# Sheet2.net
KiCad netlist of a schematic drawn in Altium Designer
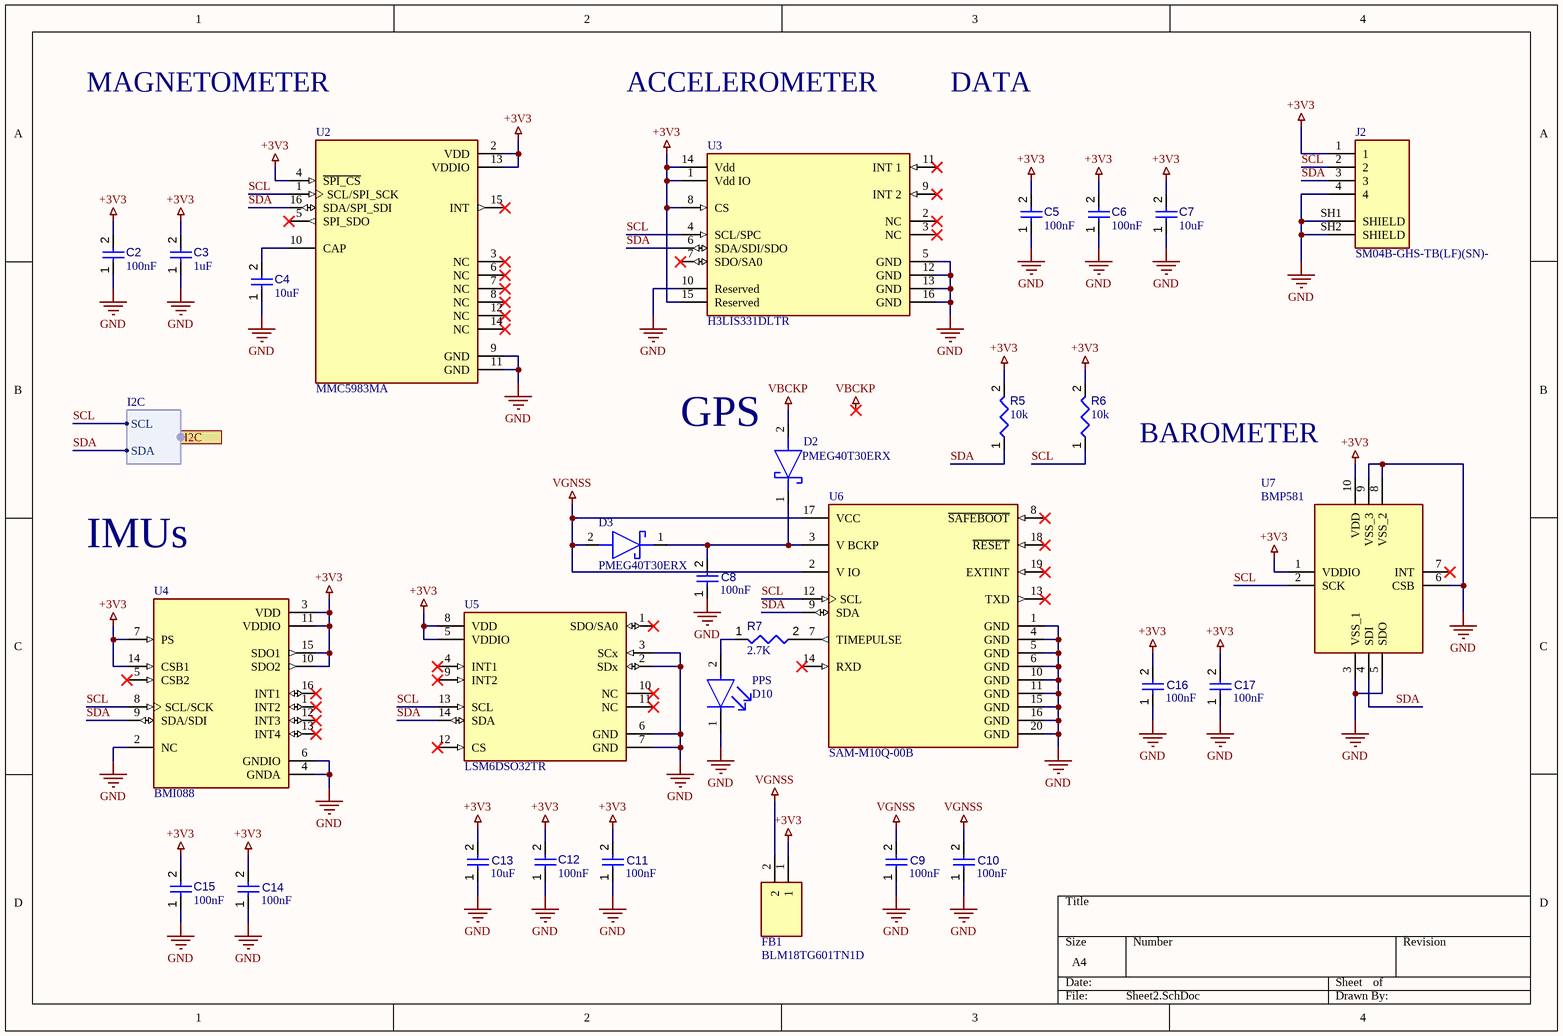
[diagram p0: Sheet2.SchDoc]

(export (version "E")
  (design (tool "Eeschema 10.0.6"))
  (components
    (comp (ref "C2")
      (value "100nF")
      (footprint "CAPC1608X90X40NL10T20")
      (description "Chip Capacitor, 100 nF, +/- 10%, 50 V, 0603 (1608 Metric)")
      (fields (field (name "TOLERANCE") "10%") (field (name "Comment") "Capacitor 100 nF +/-10% 50 V 0603"))
      (libsource (lib "PWr in Space team") (part "CAP-NP-2"))
    )
    (comp (ref "C3")
      (value "1uF")
      (footprint "CAPC1608X90X40NL10T20")
      (description "Chip Capacitor, 100 nF, +/- 10%, 50 V, 0603 (1608 Metric)")
      (fields (field (name "TOLERANCE") "10%") (field (name "Comment") "Capacitor 100 nF +/-10% 50 V 0603"))
      (libsource (lib "PWr in Space team") (part "CAP-NP-2"))
    )
    (comp (ref "C4")
      (value "10uF")
      (footprint "CAPC1608X90X40NL10T20")
      (description "Chip Capacitor, 100 nF, +/- 10%, 50 V, 0603 (1608 Metric)")
      (fields (field (name "TOLERANCE") "10%") (field (name "Comment") "Capacitor 100 nF +/-10% 50 V 0603"))
      (libsource (lib "PWr in Space team") (part "CAP-NP-2"))
    )
    (comp (ref "C5")
      (value "100nF")
      (footprint "CAPC1608X90X40NL10T20")
      (description "Chip Capacitor, 100 nF, +/- 10%, 50 V, 0603 (1608 Metric)")
      (fields (field (name "TOLERANCE") "10%") (field (name "Comment") "Capacitor 100 nF +/-10% 50 V 0603"))
      (libsource (lib "PWr in Space team") (part "CAP-NP-2"))
    )
    (comp (ref "C6")
      (value "100nF")
      (footprint "CAPC1608X90X40NL10T20")
      (description "Chip Capacitor, 100 nF, +/- 10%, 50 V, 0603 (1608 Metric)")
      (fields (field (name "TOLERANCE") "10%") (field (name "Comment") "Capacitor 100 nF +/-10% 50 V 0603"))
      (libsource (lib "PWr in Space team") (part "CAP-NP-2"))
    )
    (comp (ref "C7")
      (value "10uF")
      (footprint "CAPC1608X90X40NL10T20")
      (description "Chip Capacitor, 100 nF, +/- 10%, 50 V, 0603 (1608 Metric)")
      (fields (field (name "TOLERANCE") "10%") (field (name "Comment") "Capacitor 100 nF +/-10% 50 V 0603"))
      (libsource (lib "PWr in Space team") (part "CAP-NP-2"))
    )
    (comp (ref "C8")
      (value "100nF")
      (footprint "CAPC1608X90X40NL10T20")
      (description "Chip Capacitor, 100 nF, +/- 10%, 50 V, 0603 (1608 Metric)")
      (fields (field (name "TOLERANCE") "10%") (field (name "Comment") "Capacitor 100 nF +/-10% 50 V 0603"))
      (libsource (lib "PWr in Space team") (part "CAP-NP-2"))
    )
    (comp (ref "C9")
      (value "100nF")
      (footprint "CAPC1608X90X40NL10T20")
      (description "Chip Capacitor, 100 nF, +/- 10%, 50 V, 0603 (1608 Metric)")
      (fields (field (name "TOLERANCE") "10%") (field (name "Comment") "Capacitor 100 nF +/-10% 50 V 0603"))
      (libsource (lib "PWr in Space team") (part "CAP-NP-2"))
    )
    (comp (ref "C10")
      (value "100nF")
      (footprint "CAPC1608X90X40NL10T20")
      (description "Chip Capacitor, 100 nF, +/- 10%, 50 V, 0603 (1608 Metric)")
      (fields (field (name "TOLERANCE") "10%") (field (name "Comment") "Capacitor 100 nF +/-10% 50 V 0603"))
      (libsource (lib "PWr in Space team") (part "CAP-NP-2"))
    )
    (comp (ref "C11")
      (value "100nF")
      (footprint "CAPC1608X90X40NL10T20")
      (description "Chip Capacitor, 100 nF, +/- 10%, 50 V, 0603 (1608 Metric)")
      (fields (field (name "TOLERANCE") "10%") (field (name "Comment") "Capacitor 100 nF +/-10% 50 V 0603"))
      (libsource (lib "PWr in Space team") (part "CAP-NP-2"))
    )
    (comp (ref "C12")
      (value "100nF")
      (footprint "CAPC1608X90X40NL10T20")
      (description "Chip Capacitor, 100 nF, +/- 10%, 50 V, 0603 (1608 Metric)")
      (fields (field (name "TOLERANCE") "10%") (field (name "Comment") "Capacitor 100 nF +/-10% 50 V 0603"))
      (libsource (lib "PWr in Space team") (part "CAP-NP-2"))
    )
    (comp (ref "C13")
      (value "10uF")
      (footprint "CAPC1608X90X40NL10T20")
      (description "Chip Capacitor, 100 nF, +/- 10%, 50 V, 0603 (1608 Metric)")
      (fields (field (name "TOLERANCE") "10%") (field (name "Comment") "Capacitor 100 nF +/-10% 50 V 0603"))
      (libsource (lib "PWr in Space team") (part "CAP-NP-2"))
    )
    (comp (ref "C14")
      (value "100nF")
      (footprint "CAPC1608X90X40NL10T20")
      (description "Chip Capacitor, 100 nF, +/- 10%, 50 V, 0603 (1608 Metric)")
      (fields (field (name "TOLERANCE") "10%") (field (name "Comment") "Capacitor 100 nF +/-10% 50 V 0603"))
      (libsource (lib "PWr in Space team") (part "CAP-NP-2"))
    )
    (comp (ref "C15")
      (value "100nF")
      (footprint "CAPC1608X90X40NL10T20")
      (description "Chip Capacitor, 100 nF, +/- 10%, 50 V, 0603 (1608 Metric)")
      (fields (field (name "TOLERANCE") "10%") (field (name "Comment") "Capacitor 100 nF +/-10% 50 V 0603"))
      (libsource (lib "PWr in Space team") (part "CAP-NP-2"))
    )
    (comp (ref "C16")
      (value "100nF")
      (footprint "CAPC1608X90X40NL10T20")
      (description "Chip Capacitor, 100 nF, +/- 10%, 50 V, 0603 (1608 Metric)")
      (fields (field (name "TOLERANCE") "10%") (field (name "Comment") "Capacitor 100 nF +/-10% 50 V 0603"))
      (libsource (lib "PWr in Space team") (part "CAP-NP-2"))
    )
    (comp (ref "C17")
      (value "100nF")
      (footprint "CAPC1608X90X40NL10T20")
      (description "Chip Capacitor, 100 nF, +/- 10%, 50 V, 0603 (1608 Metric)")
      (fields (field (name "TOLERANCE") "10%") (field (name "Comment") "Capacitor 100 nF +/-10% 50 V 0603"))
      (libsource (lib "PWr in Space team") (part "CAP-NP-2"))
    )
    (comp (ref "D2")
      (value "PMEG40T30ERX")
      (footprint "SamacSys:SODFL3517X110N")
      (description "Schottky Diode")
      (fields
        (field (name "MANUFACTURER_PART_NUMBER") "PMEG60T30ELRX")
        (field (name "MOUSER PART NUMBER") "771-PMEG60T30ELRX")
      )
      (libsource (lib "*") (part "PMEG60T30ELRX"))
    )
    (comp (ref "D3")
      (value "PMEG40T30ERX")
      (footprint "SamacSys:SODFL3517X110N")
      (description "Schottky Diode")
      (fields
        (field (name "MANUFACTURER_PART_NUMBER") "PMEG60T30ELRX")
        (field (name "MOUSER PART NUMBER") "771-PMEG60T30ELRX")
      )
      (libsource (lib "*") (part "PMEG60T30ELRX"))
    )
    (comp (ref "FB1")
      (value "BLM18TG601TN1D")
      (footprint "SamacSys:BLM18EG101TH1D")
      (description "Ferrite Bead")
      (fields (field (name "MOUSER PART NUMBER") "81-BLM18TG601TN1D"))
      (libsource (lib "*") (part "BLM18TG601TN1D"))
    )
    (comp (ref "J2")
      (value "SM04B-GHS-TB(LF)(SN)-")
      (footprint "JST_SM04B-GHS-TB(LF)(SN)-")
      (description "Connector Header Surface Mount, Right Angle 4 position 0.049 _1.25mm_")
      (fields (field (name "MP") "SM04B-GHS-TB_LF__SN_-") (field (name "MF") "JST Sales"))
      (libsource (lib "PWr in Space team") (part "SM04B-GHS-TB(LF)(SN)-"))
    )
    (comp (ref "PPS")
      (value "D10")
      (footprint "FP-LTST-C191TBKT-MFG")
      (description "LED BLUE CLEAR CHIP SMD")
      (libsource (lib "Altium Content Vault") (part "8706943c75ba83719d021d2fdc84c58"))
    )
    (comp (ref "R5")
      (value "10k")
      (footprint "RESC1608X55X25ML10T15")
      (description "Chip Resistor, 10 KOhm, +/- 1%, 01 W, -55 to 155 degC, 0603 (1608 Metric)")
      (fields (field (name "POWER") "100mW") (field (name "TOLERANCE") "1%"))
      (libsource (lib "PWr in Space team") (part "RES-2"))
    )
    (comp (ref "R6")
      (value "10k")
      (footprint "RESC1608X55X25ML10T15")
      (description "Chip Resistor, 10 KOhm, +/- 1%, 01 W, -55 to 155 degC, 0603 (1608 Metric)")
      (fields (field (name "POWER") "100mW") (field (name "TOLERANCE") "1%"))
      (libsource (lib "PWr in Space team") (part "RES-2"))
    )
    (comp (ref "R7")
      (value "2.7K")
      (footprint "RESC1608X55X25ML10T15")
      (description "Chip Resistor, 10 KOhm, +/- 1%, 01 W, -55 to 155 degC, 0603 (1608 Metric)")
      (fields (field (name "POWER") "100mW") (field (name "TOLERANCE") "1%"))
      (libsource (lib "PWr in Space team") (part "RES-2"))
    )
    (comp (ref "U2")
      (value "MMC5983MA")
      (footprint "PQFN50P300X300X100-16N")
      (description "MMC5983 series Magnetic, Magnetometer Sensor Evaluation Board")
      (fields (field (name "MF") "{'manufacturer': u'Memsic Inc.'}"))
      (libsource (lib "SnapEDA_Library") (part "MMC5983MA"))
    )
    (comp (ref "U3")
      (value "H3LIS331DLTR")
      (footprint "FP-TFLGA16-7983231-MFG")
      (description "ACCEL 100-400G I2C/SPI 16TFLGA")
      (fields
        (field (name "OCTOPART") "https://octopart.com/h3lis331dltr-stmicroelectronics-29186499")
        (field (name "MANUFACTURER") "STMicroelectronics")
      )
      (libsource (lib "Altium Content Vault") (part "88bf36ed36dec8c6247366cd2bff627"))
    )
    (comp (ref "U4")
      (value "BMI088")
      (footprint "PQFN50P450X300X100-16N")
      (fields (field (name "MF") "{'manufacturer': u'Bosch Sensortec'}"))
      (libsource (lib "SnapEDA_Library") (part "BMI088"))
    )
    (comp (ref "U5")
      (value "LSM6DSO32TR")
      (footprint "FP-LGA-14L-DM00249496-MFG")
      (description "INEMO INERTIAL MODULE: 3D ACCELE")
      (libsource (lib "Altium Content Vault") (part "593856c316c551aebc7657d93cdb4f0"))
    )
    (comp (ref "U6")
      (value "SAM-M10Q-00B")
      (footprint "FP-SAM-M10Q-00B-MFG")
      (description "M10 GNSS LGA PATCH ANTENNA MOD")
      (libsource (lib "Altium Content Vault") (part "1cb72461910aa5e6ea511d063e6c758"))
    )
    (comp (ref "U7")
      (value "BMP581")
      (footprint "SamacSys:BMP581")
      (description "Undefined or Miscellaneous")
      (fields (field (name "MOUSER PART NUMBER") "262-BMP581"))
      (libsource (lib "*") (part "BMP581"))
    )
  )
  (nets
    (net (code "2") (name "+3V3") (class "Default")
      (node (ref "C11") (pin "2") (pinfunction "2_2") (pintype "passive"))
      (node (ref "C12") (pin "2") (pinfunction "2_2") (pintype "passive"))
      (node (ref "C13") (pin "2") (pinfunction "2_2") (pintype "passive"))
      (node (ref "C14") (pin "2") (pinfunction "2_2") (pintype "passive"))
      (node (ref "C15") (pin "2") (pinfunction "2_2") (pintype "passive"))
      (node (ref "C16") (pin "2") (pinfunction "2_2") (pintype "passive"))
      (node (ref "C17") (pin "2") (pinfunction "2_2") (pintype "passive"))
      (node (ref "C2") (pin "2") (pinfunction "2_2") (pintype "passive"))
      (node (ref "C3") (pin "2") (pinfunction "2_2") (pintype "passive"))
      (node (ref "C5") (pin "2") (pinfunction "2_2") (pintype "passive"))
      (node (ref "C6") (pin "2") (pinfunction "2_2") (pintype "passive"))
      (node (ref "C7") (pin "2") (pinfunction "2_2") (pintype "passive"))
      (node (ref "FB1") (pin "1") (pinfunction "1_1") (pintype "passive"))
      (node (ref "J2") (pin "1") (pinfunction "1_1") (pintype "passive"))
      (node (ref "R5") (pin "2") (pinfunction "2_2") (pintype "passive"))
      (node (ref "R6") (pin "2") (pinfunction "2_2") (pintype "passive"))
      (node (ref "U2") (pin "13") (pinfunction "VDDIO_13") (pintype "power_in"))
      (node (ref "U2") (pin "2") (pinfunction "VDD_2") (pintype "power_in"))
      (node (ref "U2") (pin "4") (pinfunction "~{SPI_CS}_4") (pintype "input"))
      (node (ref "U3") (pin "1") (pinfunction "Vdd_IO_1") (pintype "power_in"))
      (node (ref "U3") (pin "14") (pinfunction "Vdd_14") (pintype "power_in"))
      (node (ref "U3") (pin "15") (pinfunction "Reserved_15") (pintype "passive"))
      (node (ref "U3") (pin "8") (pinfunction "CS_8") (pintype "input"))
      (node (ref "U4") (pin "10") (pinfunction "SDO2_10") (pintype "output"))
      (node (ref "U4") (pin "11") (pinfunction "VDDIO_11") (pintype "power_in"))
      (node (ref "U4") (pin "14") (pinfunction "CSB1_14") (pintype "input"))
      (node (ref "U4") (pin "15") (pinfunction "SDO1_15") (pintype "output"))
      (node (ref "U4") (pin "3") (pinfunction "VDD_3") (pintype "power_in"))
      (node (ref "U4") (pin "7") (pinfunction "PS_7") (pintype "input"))
      (node (ref "U5") (pin "5") (pinfunction "VDDIO_5") (pintype "power_in"))
      (node (ref "U5") (pin "8") (pinfunction "VDD_8") (pintype "power_in"))
      (node (ref "U7") (pin "1") (pinfunction "VDDIO_1") (pintype "passive"))
      (node (ref "U7") (pin "10") (pinfunction "VDD_10") (pintype "passive"))
    )
    (net (code "3") (name "/SCL") (class "Default")
      (node (ref "J2") (pin "2") (pinfunction "2_2") (pintype "passive"))
      (node (ref "R6") (pin "1") (pinfunction "1_1") (pintype "passive"))
      (node (ref "U2") (pin "1") (pinfunction "SCL/SPI_SCK_1") (pintype "input"))
      (node (ref "U3") (pin "4") (pinfunction "SCL/SPC_4") (pintype "input"))
      (node (ref "U4") (pin "8") (pinfunction "SCL/SCK_8") (pintype "input"))
      (node (ref "U5") (pin "13") (pinfunction "SCL_13") (pintype "input"))
      (node (ref "U6") (pin "12") (pinfunction "SCL_12") (pintype "input"))
      (node (ref "U7") (pin "2") (pinfunction "SCK_2") (pintype "passive"))
    )
    (net (code "4") (name "/SDA") (class "Default")
      (node (ref "J2") (pin "3") (pinfunction "3_3") (pintype "passive"))
      (node (ref "R5") (pin "1") (pinfunction "1_1") (pintype "passive"))
      (node (ref "U2") (pin "16") (pinfunction "SDA/SPI_SDI_16") (pintype "bidirectional"))
      (node (ref "U3") (pin "6") (pinfunction "SDA/SDI/SDO_6") (pintype "bidirectional"))
      (node (ref "U4") (pin "9") (pinfunction "SDA/SDI_9") (pintype "bidirectional"))
      (node (ref "U5") (pin "14") (pinfunction "SDA_14") (pintype "bidirectional"))
      (node (ref "U6") (pin "9") (pinfunction "SDA_9") (pintype "bidirectional"))
      (node (ref "U7") (pin "4") (pinfunction "SDI_4") (pintype "passive"))
    )
    (net (code "6") (name "GND") (class "Default")
      (node (ref "C10") (pin "1") (pinfunction "1_1") (pintype "passive"))
      (node (ref "C11") (pin "1") (pinfunction "1_1") (pintype "passive"))
      (node (ref "C12") (pin "1") (pinfunction "1_1") (pintype "passive"))
      (node (ref "C13") (pin "1") (pinfunction "1_1") (pintype "passive"))
      (node (ref "C14") (pin "1") (pinfunction "1_1") (pintype "passive"))
      (node (ref "C15") (pin "1") (pinfunction "1_1") (pintype "passive"))
      (node (ref "C16") (pin "1") (pinfunction "1_1") (pintype "passive"))
      (node (ref "C17") (pin "1") (pinfunction "1_1") (pintype "passive"))
      (node (ref "C2") (pin "1") (pinfunction "1_1") (pintype "passive"))
      (node (ref "C3") (pin "1") (pinfunction "1_1") (pintype "passive"))
      (node (ref "C4") (pin "1") (pinfunction "1_1") (pintype "passive"))
      (node (ref "C5") (pin "1") (pinfunction "1_1") (pintype "passive"))
      (node (ref "C6") (pin "1") (pinfunction "1_1") (pintype "passive"))
      (node (ref "C7") (pin "1") (pinfunction "1_1") (pintype "passive"))
      (node (ref "C8") (pin "1") (pinfunction "1_1") (pintype "passive"))
      (node (ref "C9") (pin "1") (pinfunction "1_1") (pintype "passive"))
      (node (ref "J2") (pin "4") (pinfunction "4_4") (pintype "passive"))
      (node (ref "J2") (pin "SH1") (pinfunction "SHIELD_SH1") (pintype "power_in"))
      (node (ref "J2") (pin "SH2") (pinfunction "SHIELD_SH2") (pintype "power_in"))
      (node (ref "PPS") (pin "1") (pinfunction "C_1") (pintype "passive"))
      (node (ref "U2") (pin "11") (pinfunction "GND_11") (pintype "power_in"))
      (node (ref "U2") (pin "9") (pinfunction "GND_9") (pintype "power_in"))
      (node (ref "U3") (pin "10") (pinfunction "Reserved_10") (pintype "passive"))
      (node (ref "U3") (pin "12") (pinfunction "GND_12") (pintype "power_in"))
      (node (ref "U3") (pin "13") (pinfunction "GND_13") (pintype "power_in"))
      (node (ref "U3") (pin "16") (pinfunction "GND_16") (pintype "power_in"))
      (node (ref "U3") (pin "5") (pinfunction "GND_5") (pintype "power_in"))
      (node (ref "U4") (pin "2") (pinfunction "NC_2") (pintype "passive"))
      (node (ref "U4") (pin "4") (pinfunction "GNDA_4") (pintype "power_in"))
      (node (ref "U4") (pin "6") (pinfunction "GNDIO_6") (pintype "power_in"))
      (node (ref "U5") (pin "2") (pinfunction "SDx_2") (pintype "bidirectional"))
      (node (ref "U5") (pin "3") (pinfunction "SCx_3") (pintype "input"))
      (node (ref "U5") (pin "6") (pinfunction "GND_6") (pintype "power_in"))
      (node (ref "U5") (pin "7") (pinfunction "GND_7") (pintype "power_in"))
      (node (ref "U6") (pin "1") (pinfunction "GND_1") (pintype "power_in"))
      (node (ref "U6") (pin "10") (pinfunction "GND_10") (pintype "power_in"))
      (node (ref "U6") (pin "11") (pinfunction "GND_11") (pintype "power_in"))
      (node (ref "U6") (pin "15") (pinfunction "GND_15") (pintype "power_in"))
      (node (ref "U6") (pin "16") (pinfunction "GND_16") (pintype "power_in"))
      (node (ref "U6") (pin "20") (pinfunction "GND_20") (pintype "power_in"))
      (node (ref "U6") (pin "4") (pinfunction "GND_4") (pintype "power_in"))
      (node (ref "U6") (pin "5") (pinfunction "GND_5") (pintype "power_in"))
      (node (ref "U6") (pin "6") (pinfunction "GND_6") (pintype "power_in"))
      (node (ref "U7") (pin "3") (pinfunction "VSS_1_3") (pintype "passive"))
      (node (ref "U7") (pin "5") (pinfunction "SDO_5") (pintype "passive"))
      (node (ref "U7") (pin "6") (pinfunction "CSB_6") (pintype "passive"))
      (node (ref "U7") (pin "8") (pinfunction "VSS_2_8") (pintype "passive"))
      (node (ref "U7") (pin "9") (pinfunction "VSS_3_9") (pintype "passive"))
    )
    (net (code "7") (name "Net-(D2-K)") (class "Default")
      (node (ref "C8") (pin "2") (pinfunction "2_2") (pintype "passive"))
      (node (ref "D2") (pin "1") (pinfunction "K_1") (pintype "passive"))
      (node (ref "D3") (pin "1") (pinfunction "K_1") (pintype "passive"))
      (node (ref "U6") (pin "3") (pinfunction "V_BCKP_3") (pintype "power_in"))
    )
    (net (code "8") (name "Net-(PPS-A)") (class "Default")
      (node (ref "PPS") (pin "2") (pinfunction "A_2") (pintype "passive"))
      (node (ref "R7") (pin "1") (pinfunction "1_1") (pintype "passive"))
    )
    (net (code "9") (name "Net-(U2-CAP)") (class "Default")
      (node (ref "C4") (pin "2") (pinfunction "2_2") (pintype "passive"))
      (node (ref "U2") (pin "10") (pinfunction "CAP_10") (pintype "passive"))
    )
    (net (code "10") (name "Net-(U6-TIMEPULSE)") (class "Default")
      (node (ref "R7") (pin "2") (pinfunction "2_2") (pintype "passive"))
      (node (ref "U6") (pin "7") (pinfunction "TIMEPULSE_7") (pintype "output"))
    )
    (net (code "11") (name "VBCKP") (class "Default")
      (node (ref "D2") (pin "2") (pinfunction "A_2") (pintype "passive"))
    )
    (net (code "12") (name "VGNSS") (class "Default")
      (node (ref "C10") (pin "2") (pinfunction "2_2") (pintype "passive"))
      (node (ref "C9") (pin "2") (pinfunction "2_2") (pintype "passive"))
      (node (ref "D3") (pin "2") (pinfunction "A_2") (pintype "passive"))
      (node (ref "FB1") (pin "2") (pinfunction "2_2") (pintype "passive"))
      (node (ref "U6") (pin "17") (pinfunction "VCC_17") (pintype "power_in"))
      (node (ref "U6") (pin "2") (pinfunction "V_IO_2") (pintype "power_in"))
    )
    (net (code "13") (name "unconnected-(U2-INT-Pad15)") (class "Default")
      (node (ref "U2") (pin "15") (pinfunction "INT_15") (pintype "output+no_connect"))
    )
    (net (code "14") (name "unconnected-(U2-NC-Pad3)") (class "Default")
      (node (ref "U2") (pin "3") (pinfunction "NC_3") (pintype "passive+no_connect"))
    )
    (net (code "15") (name "unconnected-(U2-NC-Pad6)") (class "Default")
      (node (ref "U2") (pin "6") (pinfunction "NC_6") (pintype "passive+no_connect"))
    )
    (net (code "16") (name "unconnected-(U2-NC-Pad7)") (class "Default")
      (node (ref "U2") (pin "7") (pinfunction "NC_7") (pintype "passive+no_connect"))
    )
    (net (code "17") (name "unconnected-(U2-NC-Pad8)") (class "Default")
      (node (ref "U2") (pin "8") (pinfunction "NC_8") (pintype "passive+no_connect"))
    )
    (net (code "18") (name "unconnected-(U2-NC-Pad12)") (class "Default")
      (node (ref "U2") (pin "12") (pinfunction "NC_12") (pintype "passive+no_connect"))
    )
    (net (code "19") (name "unconnected-(U2-NC-Pad14)") (class "Default")
      (node (ref "U2") (pin "14") (pinfunction "NC_14") (pintype "passive+no_connect"))
    )
    (net (code "20") (name "unconnected-(U2-SPI_SDO-Pad5)") (class "Default")
      (node (ref "U2") (pin "5") (pinfunction "SPI_SDO_5") (pintype "output+no_connect"))
    )
    (net (code "21") (name "unconnected-(U3-INT_1-Pad11)") (class "Default")
      (node (ref "U3") (pin "11") (pinfunction "INT_1_11") (pintype "input+no_connect"))
    )
    (net (code "22") (name "unconnected-(U3-INT_2-Pad9)") (class "Default")
      (node (ref "U3") (pin "9") (pinfunction "INT_2_9") (pintype "input+no_connect"))
    )
    (net (code "23") (name "unconnected-(U3-NC-Pad2)") (class "Default")
      (node (ref "U3") (pin "2") (pinfunction "NC_2") (pintype "passive+no_connect"))
    )
    (net (code "24") (name "unconnected-(U3-NC-Pad3)") (class "Default")
      (node (ref "U3") (pin "3") (pinfunction "NC_3") (pintype "passive+no_connect"))
    )
    (net (code "25") (name "unconnected-(U3-SDO{slash}SA0-Pad7)") (class "Default")
      (node (ref "U3") (pin "7") (pinfunction "SDO/SA0_7") (pintype "bidirectional+no_connect"))
    )
    (net (code "26") (name "unconnected-(U4-CSB2-Pad5)") (class "Default")
      (node (ref "U4") (pin "5") (pinfunction "CSB2_5") (pintype "input+no_connect"))
    )
    (net (code "27") (name "unconnected-(U4-INT1-Pad16)") (class "Default")
      (node (ref "U4") (pin "16") (pinfunction "INT1_16") (pintype "bidirectional+no_connect"))
    )
    (net (code "28") (name "unconnected-(U4-INT2-Pad1)") (class "Default")
      (node (ref "U4") (pin "1") (pinfunction "INT2_1") (pintype "bidirectional+no_connect"))
    )
    (net (code "29") (name "unconnected-(U4-INT3-Pad12)") (class "Default")
      (node (ref "U4") (pin "12") (pinfunction "INT3_12") (pintype "bidirectional+no_connect"))
    )
    (net (code "30") (name "unconnected-(U4-INT4-Pad13)") (class "Default")
      (node (ref "U4") (pin "13") (pinfunction "INT4_13") (pintype "bidirectional+no_connect"))
    )
    (net (code "31") (name "unconnected-(U5-CS-Pad12)") (class "Default")
      (node (ref "U5") (pin "12") (pinfunction "CS_12") (pintype "input+no_connect"))
    )
    (net (code "32") (name "unconnected-(U5-INT1-Pad4)") (class "Default")
      (node (ref "U5") (pin "4") (pinfunction "INT1_4") (pintype "input+no_connect"))
    )
    (net (code "33") (name "unconnected-(U5-INT2-Pad9)") (class "Default")
      (node (ref "U5") (pin "9") (pinfunction "INT2_9") (pintype "input+no_connect"))
    )
    (net (code "34") (name "unconnected-(U5-NC-Pad10)") (class "Default")
      (node (ref "U5") (pin "10") (pinfunction "NC_10") (pintype "passive+no_connect"))
    )
    (net (code "35") (name "unconnected-(U5-NC-Pad11)") (class "Default")
      (node (ref "U5") (pin "11") (pinfunction "NC_11") (pintype "passive+no_connect"))
    )
    (net (code "36") (name "unconnected-(U5-SDO{slash}SA0-Pad1)") (class "Default")
      (node (ref "U5") (pin "1") (pinfunction "SDO/SA0_1") (pintype "bidirectional+no_connect"))
    )
    (net (code "37") (name "unconnected-(U6-EXTINT-Pad19)") (class "Default")
      (node (ref "U6") (pin "19") (pinfunction "EXTINT_19") (pintype "input+no_connect"))
    )
    (net (code "38") (name "unconnected-(U6-RXD-Pad14)") (class "Default")
      (node (ref "U6") (pin "14") (pinfunction "RXD_14") (pintype "input+no_connect"))
    )
    (net (code "39") (name "unconnected-(U6-TXD-Pad13)") (class "Default")
      (node (ref "U6") (pin "13") (pinfunction "TXD_13") (pintype "output+no_connect"))
    )
    (net (code "40") (name "unconnected-(U6-~{RESET}-Pad18)") (class "Default")
      (node (ref "U6") (pin "18") (pinfunction "~{RESET}_18") (pintype "input+no_connect"))
    )
    (net (code "41") (name "unconnected-(U6-~{SAFEBOOT}-Pad8)") (class "Default")
      (node (ref "U6") (pin "8") (pinfunction "~{SAFEBOOT}_8") (pintype "input+no_connect"))
    )
    (net (code "42") (name "unconnected-(U7-INT-Pad7)") (class "Default")
      (node (ref "U7") (pin "7") (pinfunction "INT_7") (pintype "passive+no_connect"))
    )
  )
)
